# control_wiring.net
KiCad netlist of a schematic drawn in EAGLE
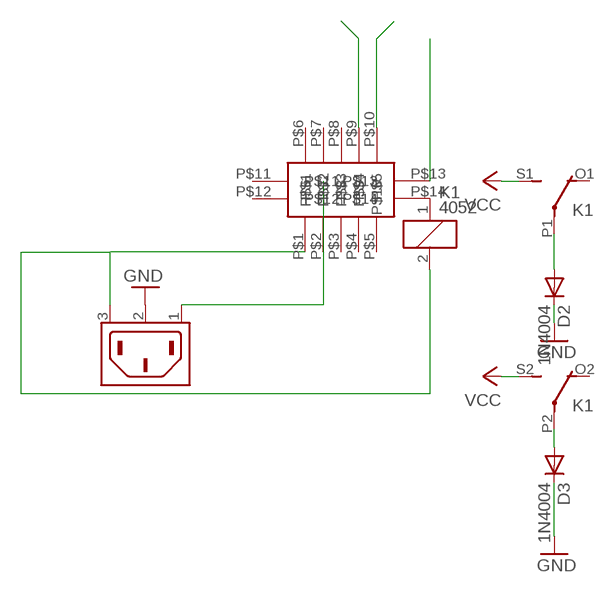
[diagram p0: schematic, sheet 1]

(export (version "E")
  (design (tool "Eeschema 10.0.6"))
  (components
    (comp (ref "D2")
      (value "1N4004")
      (footprint "eagle-import:DO41-10")
      (libsource (lib "eagle-import") (part "1N4004"))
    )
    (comp (ref "D3")
      (value "1N4004")
      (footprint "eagle-import:DO41-10")
      (libsource (lib "eagle-import") (part "1N4004"))
    )
    (comp (ref "K1")
      (value "4052")
      (footprint "eagle-import:F4052")
      (libsource (lib "eagle-import") (part "4052"))
    )
    (comp (ref "U$1")
      (value "SYL-2362")
      (footprint "eagle-import:SYL-2362")
      (libsource (lib "eagle-import") (part "SYL-2362"))
    )
    (comp (ref "X1")
      (value "6ESRM-P")
      (footprint "eagle-import:6ESRM-P")
      (fields (field (name "MF") "TYCO ELECTRONICS"))
      (libsource (lib "eagle-import") (part "6ESRM-P"))
    )
  )
  (nets
    (net (code "1") (name "/L") (class "Default")
      (node (ref "U$1") (pin "P$13") (pinfunction "P$13_P$13") (pintype "bidirectional"))
      (node (ref "U$1") (pin "P$2") (pinfunction "P$2_P$2") (pintype "bidirectional"))
      (node (ref "X1") (pin "1") (pinfunction "AC1_1") (pintype "passive"))
    )
    (net (code "2") (name "GND") (class "Default")
      (node (ref "D2") (pin "C") (pinfunction "C_C") (pintype "passive"))
      (node (ref "D3") (pin "C") (pinfunction "C_C") (pintype "passive"))
      (node (ref "X1") (pin "2") (pinfunction "SH_2") (pintype "passive"))
    )
    (net (code "3") (name "Net-(K1-Pad1)") (class "Default")
      (node (ref "K1") (pin "1") (pinfunction "1_1") (pintype "passive"))
      (node (ref "U$1") (pin "P$14") (pinfunction "P$14_P$14") (pintype "bidirectional"))
    )
    (net (code "4") (name "Net-(K1B-P)") (class "Default")
      (node (ref "D2") (pin "A") (pinfunction "A_A") (pintype "passive"))
      (node (ref "K1") (pin "P1") (pinfunction "P_P1") (pintype "passive"))
    )
    (net (code "5") (name "Net-(K1C-P)") (class "Default")
      (node (ref "D3") (pin "A") (pinfunction "A_A") (pintype "passive"))
      (node (ref "K1") (pin "P2") (pinfunction "P_P2") (pintype "passive"))
    )
    (net (code "6") (name "Net-(X1-AC2)") (class "Default")
      (node (ref "K1") (pin "2") (pinfunction "2_2") (pintype "passive"))
      (node (ref "U$1") (pin "P$1") (pinfunction "P$1_P$1") (pintype "bidirectional"))
      (node (ref "X1") (pin "3") (pinfunction "AC2_3") (pintype "passive"))
    )
    (net (code "7") (name "VCC") (class "Default")
      (node (ref "K1") (pin "S1") (pinfunction "S_S1") (pintype "passive"))
      (node (ref "K1") (pin "S2") (pinfunction "S_S2") (pintype "passive"))
    )
    (net (code "8") (name "unconnected-(K1B-O-PadO1)") (class "Default")
      (node (ref "K1") (pin "O1") (pinfunction "O_O1") (pintype "passive"))
    )
    (net (code "9") (name "unconnected-(K1C-O-PadO2)") (class "Default")
      (node (ref "K1") (pin "O2") (pinfunction "O_O2") (pintype "passive"))
    )
    (net (code "10") (name "unconnected-(U$1-PadP$3)") (class "Default")
      (node (ref "U$1") (pin "P$3") (pinfunction "P$3_P$3") (pintype "bidirectional"))
    )
    (net (code "11") (name "unconnected-(U$1-PadP$4)") (class "Default")
      (node (ref "U$1") (pin "P$4") (pinfunction "P$4_P$4") (pintype "bidirectional"))
    )
    (net (code "12") (name "unconnected-(U$1-PadP$5)") (class "Default")
      (node (ref "U$1") (pin "P$5") (pinfunction "P$5_P$5") (pintype "bidirectional"))
    )
    (net (code "13") (name "unconnected-(U$1-PadP$6)") (class "Default")
      (node (ref "U$1") (pin "P$6") (pinfunction "P$6_P$6") (pintype "bidirectional"))
    )
    (net (code "14") (name "unconnected-(U$1-PadP$7)") (class "Default")
      (node (ref "U$1") (pin "P$7") (pinfunction "P$7_P$7") (pintype "bidirectional"))
    )
    (net (code "15") (name "unconnected-(U$1-PadP$8)") (class "Default")
      (node (ref "U$1") (pin "P$8") (pinfunction "P$8_P$8") (pintype "bidirectional"))
    )
    (net (code "16") (name "unconnected-(U$1-PadP$9)") (class "Default")
      (node (ref "U$1") (pin "P$9") (pinfunction "P$9_P$9") (pintype "bidirectional"))
    )
    (net (code "17") (name "unconnected-(U$1-PadP$10)") (class "Default")
      (node (ref "U$1") (pin "P$10") (pinfunction "P$10_P$10") (pintype "bidirectional"))
    )
    (net (code "18") (name "unconnected-(U$1-PadP$11)") (class "Default")
      (node (ref "U$1") (pin "P$11") (pinfunction "P$11_P$11") (pintype "bidirectional"))
    )
    (net (code "19") (name "unconnected-(U$1-PadP$12)") (class "Default")
      (node (ref "U$1") (pin "P$12") (pinfunction "P$12_P$12") (pintype "bidirectional"))
    )
  )
)
